# CH572Q-DG-R0.net
KiCad netlist of a schematic drawn in Altium Designer
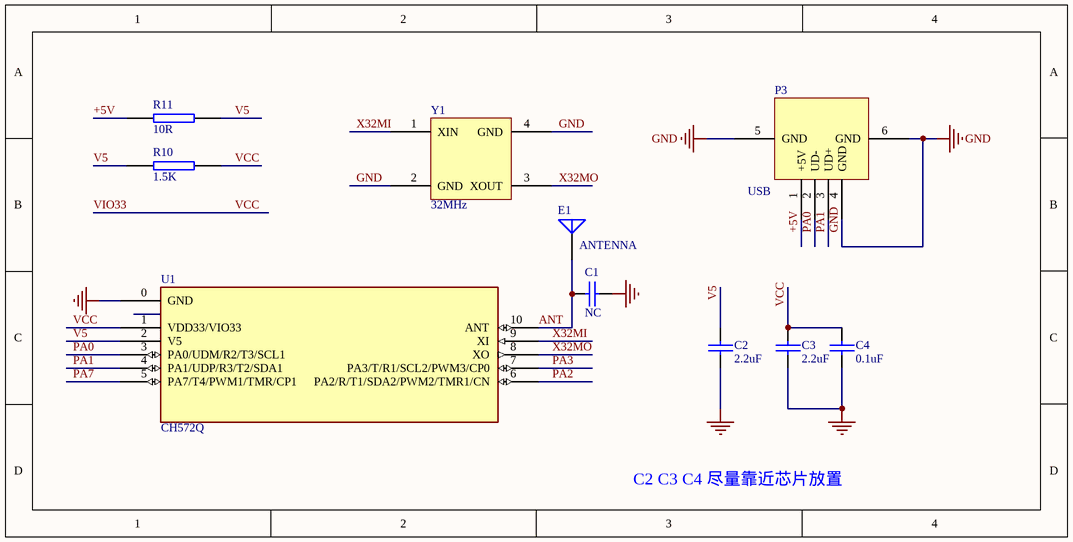
[diagram p0: CH572Q-DG-R0.SchDoc]

(export (version "E")
  (design (tool "Eeschema 10.0.6"))
  (components
    (comp (ref "C1")
      (value "NC")
      (footprint "0402_C")
      (description "Capacitor")
      (libsource (lib "*") (part "CAP"))
    )
    (comp (ref "C2")
      (value "2.2uF")
      (footprint "0402_C")
      (description "Capacitor")
      (libsource (lib "*") (part "CAP"))
    )
    (comp (ref "C3")
      (value "2.2uF")
      (footprint "0402_C")
      (description "Capacitor")
      (libsource (lib "*") (part "CAP"))
    )
    (comp (ref "C4")
      (value "0.1uF")
      (footprint "0402_C")
      (description "Capacitor")
      (libsource (lib "*") (part "CAP"))
    )
    (comp (ref "E1")
      (value "ANTENNA")
      (footprint "ANT-F-1-2.4G-0.8mmFR4")
      (description "Generic Antenna")
      (libsource (lib "*") (part "ANTENNA"))
    )
    (comp (ref "P3") (value "USB") (footprint "USBAM-4P") (libsource (lib "Schlib1") (part "USB")))
    (comp (ref "R10") (value "1.5K") (footprint "0402") (libsource (lib "*") (part "RES2")))
    (comp (ref "R11") (value "10R") (footprint "0402") (libsource (lib "*") (part "RES2")))
    (comp (ref "U1")
      (value "CH572Q")
      (footprint "DFN10_3X3")
      (description "RISC-V MCU with BLE/2.4GHz Wireless/USB/UART/I2C/PWM/CMP")
      (libsource (lib "DHXXXSCHd") (part "CH572Q"))
    )
    (comp (ref "Y1") (value "32MHz") (footprint "XT2016") (libsource (lib "wch_sch_others") (part "晶体")))
  )
  (nets
    (net (code "1") (name "/+5V") (class "Default")
      (node (ref "P3") (pin "1") (pinfunction "+5V_1") (pintype "passive"))
      (node (ref "R11") (pin "2") (pinfunction "2_2") (pintype "passive"))
    )
    (net (code "2") (name "/ANT") (class "Default")
      (node (ref "C1") (pin "1") (pinfunction "1_1") (pintype "passive"))
      (node (ref "E1") (pin "1") (pinfunction "A_1") (pintype "passive"))
      (node (ref "U1") (pin "10") (pinfunction "ANT_10") (pintype "bidirectional"))
    )
    (net (code "3") (name "/PA0") (class "Default")
      (node (ref "P3") (pin "2") (pinfunction "UD-_2") (pintype "passive"))
      (node (ref "U1") (pin "3") (pinfunction "PA0/UDM/R2/T3/SCL1_3") (pintype "bidirectional"))
    )
    (net (code "4") (name "/PA1") (class "Default")
      (node (ref "P3") (pin "3") (pinfunction "UD+_3") (pintype "passive"))
      (node (ref "U1") (pin "4") (pinfunction "PA1/UDP/R3/T2/SDA1_4") (pintype "bidirectional"))
    )
    (net (code "5") (name "/PA2") (class "Default")
      (node (ref "U1") (pin "6") (pinfunction "PA2/R/T1/SDA2/PWM2/TMR1/CN_6") (pintype "bidirectional"))
    )
    (net (code "6") (name "/PA3") (class "Default")
      (node (ref "U1") (pin "7") (pinfunction "PA3/T/R1/SCL2/PWM3/CP0_7") (pintype "bidirectional"))
    )
    (net (code "7") (name "/PA7") (class "Default")
      (node (ref "U1") (pin "5") (pinfunction "PA7/T4/PWM1/TMR/CP1_5") (pintype "bidirectional"))
    )
    (net (code "8") (name "/V5") (class "Default")
      (node (ref "C2") (pin "1") (pinfunction "1_1") (pintype "passive"))
      (node (ref "R10") (pin "2") (pinfunction "2_2") (pintype "passive"))
      (node (ref "R11") (pin "1") (pinfunction "1_1") (pintype "passive"))
      (node (ref "U1") (pin "2") (pinfunction "V5_2") (pintype "power_in"))
    )
    (net (code "9") (name "/VCC") (class "Default")
      (node (ref "C3") (pin "1") (pinfunction "1_1") (pintype "passive"))
      (node (ref "C4") (pin "1") (pinfunction "1_1") (pintype "passive"))
      (node (ref "R10") (pin "1") (pinfunction "1_1") (pintype "passive"))
      (node (ref "U1") (pin "1") (pinfunction "VDD33/VIO33_1") (pintype "power_in"))
    )
    (net (code "10") (name "/X32MI") (class "Default")
      (node (ref "U1") (pin "9") (pinfunction "XI_9") (pintype "input"))
      (node (ref "Y1") (pin "1") (pinfunction "XIN_1") (pintype "passive"))
    )
    (net (code "11") (name "/X32MO") (class "Default")
      (node (ref "U1") (pin "8") (pinfunction "XO_8") (pintype "output"))
      (node (ref "Y1") (pin "3") (pinfunction "XOUT_3") (pintype "passive"))
    )
    (net (code "12") (name "GND") (class "Default")
      (node (ref "C1") (pin "2") (pinfunction "2_2") (pintype "passive"))
      (node (ref "C2") (pin "2") (pinfunction "2_2") (pintype "passive"))
      (node (ref "C3") (pin "2") (pinfunction "2_2") (pintype "passive"))
      (node (ref "C4") (pin "2") (pinfunction "2_2") (pintype "passive"))
      (node (ref "P3") (pin "4") (pinfunction "GND_4") (pintype "passive"))
      (node (ref "P3") (pin "5") (pinfunction "GND_5") (pintype "passive"))
      (node (ref "P3") (pin "6") (pinfunction "GND_6") (pintype "passive"))
      (node (ref "U1") (pin "0") (pinfunction "GND_0") (pintype "power_in"))
      (node (ref "Y1") (pin "2") (pinfunction "GND_2") (pintype "passive"))
      (node (ref "Y1") (pin "4") (pinfunction "GND_4") (pintype "passive"))
    )
  )
)
